# Processor_Board.net
KiCad netlist of a schematic drawn in EAGLE
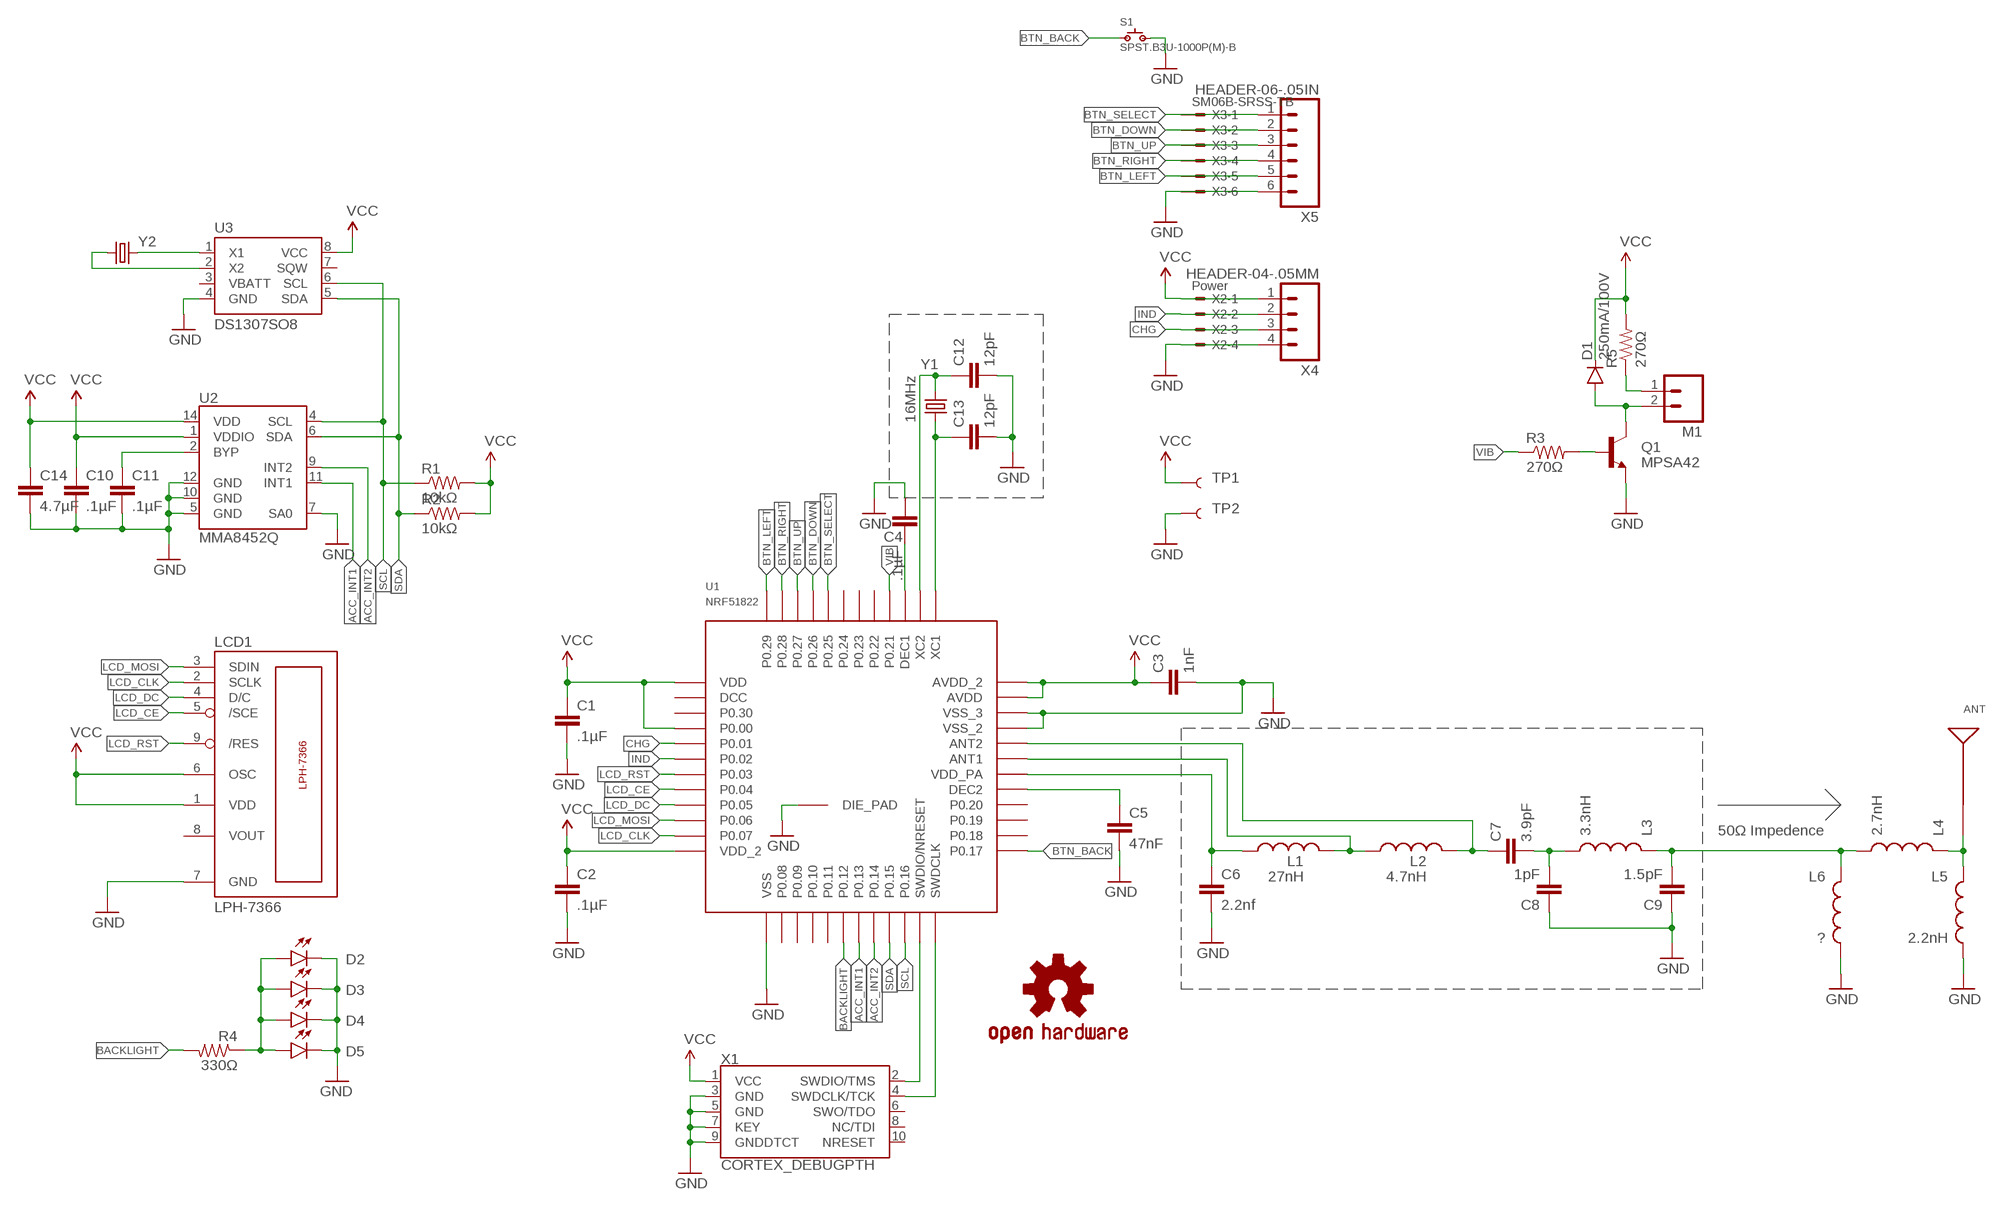
[diagram p0: schematic, sheet 1]

(export (version "E")
  (design (tool "Eeschema 10.0.6"))
  (components
    (comp (ref "ANT")
      (value "ANTENNA_CHIP2450AT43B100")
      (footprint "eagle-import:AT43B")
      (fields (field (name "MANUFACTURER") "Johanson Technology"))
      (libsource (lib "eagle-import") (part "ANTENNA_CHIP2450AT43B100"))
    )
    (comp (ref "C1")
      (value ".1µF")
      (footprint "eagle-import:0805")
      (libsource (lib "eagle-import") (part "CAP0805"))
    )
    (comp (ref "C2")
      (value ".1µF")
      (footprint "eagle-import:0805")
      (libsource (lib "eagle-import") (part "CAP0805"))
    )
    (comp (ref "C3")
      (value "1nF")
      (footprint "eagle-import:0805")
      (libsource (lib "eagle-import") (part "CAP0805"))
    )
    (comp (ref "C4")
      (value ".1µF")
      (footprint "eagle-import:0805")
      (libsource (lib "eagle-import") (part "CAP0805"))
    )
    (comp (ref "C5")
      (value "47nF")
      (footprint "eagle-import:0805")
      (libsource (lib "eagle-import") (part "CAP0805"))
    )
    (comp (ref "C6")
      (value "2.2nf")
      (footprint "eagle-import:0805")
      (libsource (lib "eagle-import") (part "CAP0805"))
    )
    (comp (ref "C7")
      (value "3.9pF")
      (footprint "eagle-import:0805")
      (libsource (lib "eagle-import") (part "CAP0805"))
    )
    (comp (ref "C8")
      (value "1pF")
      (footprint "eagle-import:0805")
      (libsource (lib "eagle-import") (part "CAP0805"))
    )
    (comp (ref "C9")
      (value "1.5pF")
      (footprint "eagle-import:0805")
      (libsource (lib "eagle-import") (part "CAP0805"))
    )
    (comp (ref "C10")
      (value ".1µF")
      (footprint "eagle-import:0805")
      (libsource (lib "eagle-import") (part "CAP0805"))
    )
    (comp (ref "C11")
      (value ".1µF")
      (footprint "eagle-import:0805")
      (libsource (lib "eagle-import") (part "CAP0805"))
    )
    (comp (ref "C12")
      (value "12pF")
      (footprint "eagle-import:0805")
      (libsource (lib "eagle-import") (part "CAP0805"))
    )
    (comp (ref "C13")
      (value "12pF")
      (footprint "eagle-import:0805")
      (libsource (lib "eagle-import") (part "CAP0805"))
    )
    (comp (ref "C14")
      (value "4.7µF")
      (footprint "eagle-import:0805")
      (libsource (lib "eagle-import") (part "CAP0805"))
    )
    (comp (ref "D1")
      (value "250mA/100V")
      (footprint "eagle-import:SOD-323")
      (libsource (lib "eagle-import") (part "DIODEBAS16"))
    )
    (comp (ref "D2")
      (value "LED1206")
      (footprint "eagle-import:LED-1206")
      (libsource (lib "eagle-import") (part "LED1206"))
    )
    (comp (ref "D3")
      (value "LED1206")
      (footprint "eagle-import:LED-1206")
      (libsource (lib "eagle-import") (part "LED1206"))
    )
    (comp (ref "D4")
      (value "LED1206")
      (footprint "eagle-import:LED-1206")
      (libsource (lib "eagle-import") (part "LED1206"))
    )
    (comp (ref "D5")
      (value "LED1206")
      (footprint "eagle-import:LED-1206")
      (libsource (lib "eagle-import") (part "LED1206"))
    )
    (comp (ref "L1")
      (value "27nH")
      (footprint "eagle-import:0805")
      (libsource (lib "eagle-import") (part "INDUCTOR0805"))
    )
    (comp (ref "L2")
      (value "4.7nH")
      (footprint "eagle-import:0805")
      (libsource (lib "eagle-import") (part "INDUCTOR0805"))
    )
    (comp (ref "L3")
      (value "3.3nH")
      (footprint "eagle-import:0805")
      (libsource (lib "eagle-import") (part "INDUCTOR0805"))
    )
    (comp (ref "L4")
      (value "2.7nH")
      (footprint "eagle-import:0805")
      (libsource (lib "eagle-import") (part "INDUCTOR0805"))
    )
    (comp (ref "L5")
      (value "2.2nH")
      (footprint "eagle-import:0805")
      (libsource (lib "eagle-import") (part "INDUCTOR0805"))
    )
    (comp (ref "L6")
      (value "?")
      (footprint "eagle-import:0805")
      (libsource (lib "eagle-import") (part "INDUCTOR0805"))
    )
    (comp (ref "LCD1")
      (value "LPH-7366")
      (footprint "eagle-import:LPH-7366")
      (libsource (lib "eagle-import") (part "LPH-7366"))
    )
    (comp (ref "LOGO1")
      (value "OSHW-LOGOL-COPPER")
      (footprint "eagle-import:OSHW-LOGO-L_COPPER")
      (libsource (lib "eagle-import") (part "OSHW-LOGOL-COPPER"))
    )
    (comp (ref "M1")
      (value "M021X02_NO_SILK")
      (footprint "eagle-import:1X02_NO_SILK")
      (libsource (lib "eagle-import") (part "M021X02_NO_SILK"))
    )
    (comp (ref "Q1")
      (value "MPSA42")
      (footprint "eagle-import:SOT23-3")
      (libsource (lib "eagle-import") (part "TRANSISTOR_NPNMPSA42"))
    )
    (comp (ref "R1")
      (value "10kΩ")
      (footprint "eagle-import:0805")
      (libsource (lib "eagle-import") (part "RESISTOR0805-RES"))
    )
    (comp (ref "R2")
      (value "10kΩ")
      (footprint "eagle-import:0805")
      (libsource (lib "eagle-import") (part "RESISTOR0805-RES"))
    )
    (comp (ref "R3")
      (value "270Ω")
      (footprint "eagle-import:0805")
      (libsource (lib "eagle-import") (part "RESISTOR0805-RES"))
    )
    (comp (ref "R4")
      (value "330Ω")
      (footprint "eagle-import:0805")
      (libsource (lib "eagle-import") (part "RESISTOR0805-RES"))
    )
    (comp (ref "R5")
      (value "270Ω")
      (footprint "eagle-import:0805")
      (libsource (lib "eagle-import") (part "RESISTOR0805-RES"))
    )
    (comp (ref "S1")
      (value "SPST.B3U-1000P(M)-B")
      (footprint "eagle-import:B3U-1000P(M)-B")
      (libsource (lib "eagle-import") (part "SPST.B3U-1000P(M)-B"))
    )
    (comp (ref "TP1")
      (value "TEST-POINT3")
      (footprint "eagle-import:PAD.03X.03")
      (libsource (lib "eagle-import") (part "TEST-POINT3"))
    )
    (comp (ref "TP2")
      (value "TEST-POINT3")
      (footprint "eagle-import:PAD.03X.03")
      (libsource (lib "eagle-import") (part "TEST-POINT3"))
    )
    (comp (ref "U1")
      (value "NRF51822")
      (footprint "eagle-import:QFN48")
      (libsource (lib "eagle-import") (part "NRF51822"))
    )
    (comp (ref "U2")
      (value "MMA8452Q")
      (footprint "eagle-import:QFN-16_0.5MM")
      (libsource (lib "eagle-import") (part "MMA8452Q"))
    )
    (comp (ref "U3")
      (value "DS1307SO8")
      (footprint "eagle-import:SO08")
      (libsource (lib "eagle-import") (part "DS1307SO8"))
    )
    (comp (ref "X1")
      (value "CORTEX_DEBUGPTH")
      (footprint "eagle-import:2X5-PTH-1.27MM")
      (libsource (lib "eagle-import") (part "CORTEX_DEBUGPTH"))
    )
    (comp (ref "X2")
      (value "Power")
      (footprint "eagle-import:SM04B-SRSS-TB")
      (libsource (lib "eagle-import") (part "?M04B-SRSS-TBS"))
    )
    (comp (ref "X3")
      (value "SM06B-SRSS-TB")
      (footprint "eagle-import:SM06B-SRSS-TB")
      (libsource (lib "eagle-import") (part "?M06B-SRSS-TBS"))
    )
    (comp (ref "X4")
      (value "HEADER-04-.05MM")
      (footprint "eagle-import:HEADER-04-.05IN")
      (libsource (lib "eagle-import") (part "HEADER-04-.05MM"))
    )
    (comp (ref "X5")
      (value "HEADER-06-.05IN")
      (footprint "eagle-import:HEADER-06-.05IN")
      (libsource (lib "eagle-import") (part "HEADER-06-.05IN"))
    )
    (comp (ref "Y1")
      (value "16MHz")
      (footprint "eagle-import:CRYSTAL-SMD-5X3")
      (libsource (lib "eagle-import") (part "CRYSTALCRYSTAL-SMD-5X3-16MHZ"))
    )
    (comp (ref "Y2")
      (value "CRYSTAL32-SMD-MELF")
      (footprint "eagle-import:CRYSTAL-32KHZ-SMD-MELF")
      (libsource (lib "eagle-import") (part "CRYSTAL32-SMD-MELF"))
    )
  )
  (nets
    (net (code "1") (name "ACC_INT1") (class "Default")
      (node (ref "U1") (pin "19") (pinfunction "P0.13_19") (pintype "bidirectional"))
      (node (ref "U2") (pin "11") (pinfunction "INT1_11") (pintype "bidirectional"))
    )
    (net (code "2") (name "ACC_INT2") (class "Default")
      (node (ref "U1") (pin "20") (pinfunction "P0.14_20") (pintype "bidirectional"))
      (node (ref "U2") (pin "9") (pinfunction "INT2_9") (pintype "bidirectional"))
    )
    (net (code "3") (name "BACKLIGHT") (class "Default")
      (node (ref "R4") (pin "2") (pinfunction "2_2") (pintype "passive"))
      (node (ref "U1") (pin "18") (pinfunction "P0.12_18") (pintype "bidirectional"))
    )
    (net (code "4") (name "BTN_BACK") (class "Default")
      (node (ref "S1") (pin "1") (pinfunction "1_1") (pintype "bidirectional"))
      (node (ref "U1") (pin "25") (pinfunction "P0.17_25") (pintype "bidirectional"))
    )
    (net (code "5") (name "BTN_DOWN") (class "Default")
      (node (ref "U1") (pin "45") (pinfunction "P0.26_45") (pintype "bidirectional"))
      (node (ref "X3") (pin "2") (pinfunction "S_2") (pintype "passive"))
      (node (ref "X5") (pin "2") (pinfunction "2_2") (pintype "passive"))
    )
    (net (code "6") (name "BTN_LEFT") (class "Default")
      (node (ref "U1") (pin "48") (pinfunction "P0.29_48") (pintype "bidirectional"))
      (node (ref "X3") (pin "5") (pinfunction "S_5") (pintype "passive"))
      (node (ref "X5") (pin "5") (pinfunction "5_5") (pintype "passive"))
    )
    (net (code "7") (name "BTN_RIGHT") (class "Default")
      (node (ref "U1") (pin "47") (pinfunction "P0.28_47") (pintype "bidirectional"))
      (node (ref "X3") (pin "4") (pinfunction "S_4") (pintype "passive"))
      (node (ref "X5") (pin "4") (pinfunction "4_4") (pintype "passive"))
    )
    (net (code "8") (name "BTN_SELECT") (class "Default")
      (node (ref "U1") (pin "44") (pinfunction "P0.25_44") (pintype "bidirectional"))
      (node (ref "X3") (pin "1") (pinfunction "S_1") (pintype "passive"))
      (node (ref "X5") (pin "1") (pinfunction "1_1") (pintype "passive"))
    )
    (net (code "9") (name "BTN_UP") (class "Default")
      (node (ref "U1") (pin "46") (pinfunction "P0.27_46") (pintype "bidirectional"))
      (node (ref "X3") (pin "3") (pinfunction "S_3") (pintype "passive"))
      (node (ref "X5") (pin "3") (pinfunction "3_3") (pintype "passive"))
    )
    (net (code "10") (name "CHG") (class "Default")
      (node (ref "U1") (pin "5") (pinfunction "P0.01_5") (pintype "bidirectional"))
      (node (ref "X2") (pin "3") (pinfunction "S_3") (pintype "passive"))
      (node (ref "X4") (pin "3") (pinfunction "3_3") (pintype "passive"))
    )
    (net (code "11") (name "GND") (class "Default")
      (node (ref "C1") (pin "2") (pinfunction "2_2") (pintype "passive"))
      (node (ref "C10") (pin "2") (pinfunction "2_2") (pintype "passive"))
      (node (ref "C11") (pin "2") (pinfunction "2_2") (pintype "passive"))
      (node (ref "C12") (pin "1") (pinfunction "1_1") (pintype "passive"))
      (node (ref "C13") (pin "1") (pinfunction "1_1") (pintype "passive"))
      (node (ref "C14") (pin "2") (pinfunction "2_2") (pintype "passive"))
      (node (ref "C2") (pin "2") (pinfunction "2_2") (pintype "passive"))
      (node (ref "C3") (pin "2") (pinfunction "2_2") (pintype "passive"))
      (node (ref "C4") (pin "1") (pinfunction "1_1") (pintype "passive"))
      (node (ref "C5") (pin "2") (pinfunction "2_2") (pintype "passive"))
      (node (ref "C6") (pin "2") (pinfunction "2_2") (pintype "passive"))
      (node (ref "C8") (pin "1") (pinfunction "1_1") (pintype "passive"))
      (node (ref "C9") (pin "1") (pinfunction "1_1") (pintype "passive"))
      (node (ref "D2") (pin "C") (pinfunction "C_C") (pintype "passive"))
      (node (ref "D3") (pin "C") (pinfunction "C_C") (pintype "passive"))
      (node (ref "D4") (pin "C") (pinfunction "C_C") (pintype "passive"))
      (node (ref "D5") (pin "C") (pinfunction "C_C") (pintype "passive"))
      (node (ref "L5") (pin "2") (pinfunction "2_2") (pintype "passive"))
      (node (ref "L6") (pin "2") (pinfunction "2_2") (pintype "passive"))
      (node (ref "LCD1") (pin "7") (pinfunction "GND_7") (pintype "power_in"))
      (node (ref "Q1") (pin "2") (pinfunction "E_2") (pintype "passive"))
      (node (ref "S1") (pin "2") (pinfunction "2_2") (pintype "bidirectional"))
      (node (ref "TP2") (pin "P$1") (pinfunction "1_P$1") (pintype "bidirectional"))
      (node (ref "U1") (pin "13") (pinfunction "VSS_13") (pintype "bidirectional"))
      (node (ref "U1") (pin "33") (pinfunction "VSS_2_33") (pintype "bidirectional"))
      (node (ref "U1") (pin "34") (pinfunction "VSS_3_34") (pintype "bidirectional"))
      (node (ref "U1") (pin "GND") (pinfunction "DIE_PAD_GND") (pintype "bidirectional"))
      (node (ref "U2") (pin "10") (pinfunction "GND_10") (pintype "bidirectional"))
      (node (ref "U2") (pin "12") (pinfunction "GND_12") (pintype "bidirectional"))
      (node (ref "U2") (pin "5") (pinfunction "GND_5") (pintype "bidirectional"))
      (node (ref "U2") (pin "7") (pinfunction "SA0_7") (pintype "bidirectional"))
      (node (ref "U3") (pin "4") (pinfunction "GND_4") (pintype "bidirectional"))
      (node (ref "X1") (pin "3") (pinfunction "GND_3") (pintype "bidirectional"))
      (node (ref "X1") (pin "5") (pinfunction "GND_5") (pintype "bidirectional"))
      (node (ref "X1") (pin "7") (pinfunction "KEY_7") (pintype "bidirectional"))
      (node (ref "X1") (pin "9") (pinfunction "GNDDTCT_9") (pintype "bidirectional"))
      (node (ref "X2") (pin "4") (pinfunction "S_4") (pintype "passive"))
      (node (ref "X3") (pin "6") (pinfunction "S_6") (pintype "passive"))
      (node (ref "X4") (pin "4") (pinfunction "4_4") (pintype "passive"))
      (node (ref "X5") (pin "6") (pinfunction "6_6") (pintype "passive"))
    )
    (net (code "12") (name "IND") (class "Default")
      (node (ref "U1") (pin "6") (pinfunction "P0.02_6") (pintype "bidirectional"))
      (node (ref "X2") (pin "2") (pinfunction "S_2") (pintype "passive"))
      (node (ref "X4") (pin "2") (pinfunction "2_2") (pintype "passive"))
    )
    (net (code "13") (name "LCD_CE") (class "Default")
      (node (ref "LCD1") (pin "5") (pinfunction "/SCE_5") (pintype "input"))
      (node (ref "U1") (pin "8") (pinfunction "P0.04_8") (pintype "bidirectional"))
    )
    (net (code "14") (name "LCD_CLK") (class "Default")
      (node (ref "LCD1") (pin "2") (pinfunction "SCLK_2") (pintype "input"))
      (node (ref "U1") (pin "11") (pinfunction "P0.07_11") (pintype "bidirectional"))
    )
    (net (code "15") (name "LCD_DC") (class "Default")
      (node (ref "LCD1") (pin "4") (pinfunction "D/C_4") (pintype "input"))
      (node (ref "U1") (pin "9") (pinfunction "P0.05_9") (pintype "bidirectional"))
    )
    (net (code "16") (name "LCD_MOSI") (class "Default")
      (node (ref "LCD1") (pin "3") (pinfunction "SDIN_3") (pintype "input"))
      (node (ref "U1") (pin "10") (pinfunction "P0.06_10") (pintype "bidirectional"))
    )
    (net (code "17") (name "LCD_RST") (class "Default")
      (node (ref "LCD1") (pin "9") (pinfunction "/RES_9") (pintype "input"))
      (node (ref "U1") (pin "7") (pinfunction "P0.03_7") (pintype "bidirectional"))
    )
    (net (code "18") (name "Net-(ANT-PadANT)") (class "Default")
      (node (ref "ANT") (pin "ANT") (pinfunction "ANT_ANT") (pintype "bidirectional"))
      (node (ref "L4") (pin "1") (pinfunction "1_1") (pintype "passive"))
      (node (ref "L5") (pin "1") (pinfunction "1_1") (pintype "passive"))
    )
    (net (code "19") (name "Net-(C7-Pad2)") (class "Default")
      (node (ref "C7") (pin "2") (pinfunction "2_2") (pintype "passive"))
      (node (ref "C8") (pin "2") (pinfunction "2_2") (pintype "passive"))
      (node (ref "L3") (pin "2") (pinfunction "2_2") (pintype "passive"))
    )
    (net (code "20") (name "Net-(C9-Pad2)") (class "Default")
      (node (ref "C9") (pin "2") (pinfunction "2_2") (pintype "passive"))
      (node (ref "L3") (pin "1") (pinfunction "1_1") (pintype "passive"))
      (node (ref "L4") (pin "2") (pinfunction "2_2") (pintype "passive"))
      (node (ref "L6") (pin "1") (pinfunction "1_1") (pintype "passive"))
    )
    (net (code "21") (name "Net-(D2-PadA)") (class "Default")
      (node (ref "D2") (pin "A") (pinfunction "A_A") (pintype "passive"))
      (node (ref "D3") (pin "A") (pinfunction "A_A") (pintype "passive"))
      (node (ref "D4") (pin "A") (pinfunction "A_A") (pintype "passive"))
      (node (ref "D5") (pin "A") (pinfunction "A_A") (pintype "passive"))
      (node (ref "R4") (pin "1") (pinfunction "1_1") (pintype "passive"))
    )
    (net (code "22") (name "Net-(M1-Pad1)") (class "Default")
      (node (ref "M1") (pin "1") (pinfunction "1_1") (pintype "passive"))
      (node (ref "R5") (pin "1") (pinfunction "1_1") (pintype "passive"))
    )
    (net (code "23") (name "Net-(Q1-B)") (class "Default")
      (node (ref "Q1") (pin "1") (pinfunction "B_1") (pintype "passive"))
      (node (ref "R3") (pin "2") (pinfunction "2_2") (pintype "passive"))
    )
    (net (code "24") (name "Net-(Q1-C)") (class "Default")
      (node (ref "D1") (pin "A") (pinfunction "A_A") (pintype "passive"))
      (node (ref "M1") (pin "2") (pinfunction "2_2") (pintype "passive"))
      (node (ref "Q1") (pin "3") (pinfunction "C_3") (pintype "passive"))
    )
    (net (code "25") (name "Net-(U1-ANT1)") (class "Default")
      (node (ref "L1") (pin "1") (pinfunction "1_1") (pintype "passive"))
      (node (ref "L2") (pin "2") (pinfunction "2_2") (pintype "passive"))
      (node (ref "U1") (pin "31") (pinfunction "ANT1_31") (pintype "bidirectional"))
    )
    (net (code "26") (name "Net-(U1-ANT2)") (class "Default")
      (node (ref "C7") (pin "1") (pinfunction "1_1") (pintype "passive"))
      (node (ref "L2") (pin "1") (pinfunction "1_1") (pintype "passive"))
      (node (ref "U1") (pin "32") (pinfunction "ANT2_32") (pintype "bidirectional"))
    )
    (net (code "27") (name "Net-(U1-DEC1)") (class "Default")
      (node (ref "C4") (pin "2") (pinfunction "2_2") (pintype "passive"))
      (node (ref "U1") (pin "39") (pinfunction "DEC1_39") (pintype "bidirectional"))
    )
    (net (code "28") (name "Net-(U1-DEC2)") (class "Default")
      (node (ref "C5") (pin "1") (pinfunction "1_1") (pintype "passive"))
      (node (ref "U1") (pin "29") (pinfunction "DEC2_29") (pintype "bidirectional"))
    )
    (net (code "29") (name "Net-(U1-SWDCLK)") (class "Default")
      (node (ref "U1") (pin "24") (pinfunction "SWDCLK_24") (pintype "bidirectional"))
      (node (ref "X1") (pin "4") (pinfunction "SWDCLK/TCK_4") (pintype "bidirectional"))
    )
    (net (code "30") (name "Net-(U1-SWDIO{slash}NRESET)") (class "Default")
      (node (ref "U1") (pin "23") (pinfunction "SWDIO/NRESET_23") (pintype "bidirectional"))
      (node (ref "X1") (pin "2") (pinfunction "SWDIO/TMS_2") (pintype "bidirectional"))
    )
    (net (code "31") (name "Net-(U1-VDD_PA)") (class "Default")
      (node (ref "C6") (pin "1") (pinfunction "1_1") (pintype "passive"))
      (node (ref "L1") (pin "2") (pinfunction "2_2") (pintype "passive"))
      (node (ref "U1") (pin "30") (pinfunction "VDD_PA_30") (pintype "bidirectional"))
    )
    (net (code "32") (name "Net-(U1-XC1)") (class "Default")
      (node (ref "C13") (pin "2") (pinfunction "2_2") (pintype "passive"))
      (node (ref "U1") (pin "37") (pinfunction "XC1_37") (pintype "bidirectional"))
      (node (ref "Y1") (pin "1") (pinfunction "1_1") (pintype "passive"))
    )
    (net (code "33") (name "Net-(U1-XC2)") (class "Default")
      (node (ref "C12") (pin "2") (pinfunction "2_2") (pintype "passive"))
      (node (ref "U1") (pin "38") (pinfunction "XC2_38") (pintype "bidirectional"))
      (node (ref "Y1") (pin "3") (pinfunction "2_3") (pintype "passive"))
    )
    (net (code "34") (name "Net-(U2-BYP)") (class "Default")
      (node (ref "C11") (pin "1") (pinfunction "1_1") (pintype "passive"))
      (node (ref "U2") (pin "2") (pinfunction "BYP_2") (pintype "bidirectional"))
    )
    (net (code "35") (name "Net-(U3-X1)") (class "Default")
      (node (ref "U3") (pin "1") (pinfunction "X1_1") (pintype "bidirectional"))
      (node (ref "Y2") (pin "X2") (pinfunction "2_X2") (pintype "passive"))
    )
    (net (code "36") (name "Net-(U3-X2)") (class "Default")
      (node (ref "U3") (pin "2") (pinfunction "X2_2") (pintype "bidirectional"))
      (node (ref "Y2") (pin "X1") (pinfunction "1_X1") (pintype "passive"))
    )
    (net (code "37") (name "SCL") (class "Default")
      (node (ref "R1") (pin "1") (pinfunction "1_1") (pintype "passive"))
      (node (ref "U1") (pin "22") (pinfunction "P0.16_22") (pintype "bidirectional"))
      (node (ref "U2") (pin "4") (pinfunction "SCL_4") (pintype "bidirectional"))
      (node (ref "U3") (pin "6") (pinfunction "SCL_6") (pintype "bidirectional"))
    )
    (net (code "38") (name "SDA") (class "Default")
      (node (ref "R2") (pin "1") (pinfunction "1_1") (pintype "passive"))
      (node (ref "U1") (pin "21") (pinfunction "P0.15_21") (pintype "bidirectional"))
      (node (ref "U2") (pin "6") (pinfunction "SDA_6") (pintype "bidirectional"))
      (node (ref "U3") (pin "5") (pinfunction "SDA_5") (pintype "bidirectional"))
    )
    (net (code "39") (name "VCC") (class "Default")
      (node (ref "C1") (pin "1") (pinfunction "1_1") (pintype "passive"))
      (node (ref "C10") (pin "1") (pinfunction "1_1") (pintype "passive"))
      (node (ref "C14") (pin "1") (pinfunction "1_1") (pintype "passive"))
      (node (ref "C2") (pin "1") (pinfunction "1_1") (pintype "passive"))
      (node (ref "C3") (pin "1") (pinfunction "1_1") (pintype "passive"))
      (node (ref "D1") (pin "C") (pinfunction "C_C") (pintype "passive"))
      (node (ref "LCD1") (pin "1") (pinfunction "VDD_1") (pintype "power_in"))
      (node (ref "LCD1") (pin "6") (pinfunction "OSC_6") (pintype "passive"))
      (node (ref "R1") (pin "2") (pinfunction "2_2") (pintype "passive"))
      (node (ref "R2") (pin "2") (pinfunction "2_2") (pintype "passive"))
      (node (ref "R5") (pin "2") (pinfunction "2_2") (pintype "passive"))
      (node (ref "TP1") (pin "P$1") (pinfunction "1_P$1") (pintype "bidirectional"))
      (node (ref "U1") (pin "1") (pinfunction "VDD_1") (pintype "bidirectional"))
      (node (ref "U1") (pin "12") (pinfunction "VDD_2_12") (pintype "bidirectional"))
      (node (ref "U1") (pin "35") (pinfunction "AVDD_35") (pintype "bidirectional"))
      (node (ref "U1") (pin "36") (pinfunction "AVDD_2_36") (pintype "bidirectional"))
      (node (ref "U1") (pin "4") (pinfunction "P0.00_4") (pintype "bidirectional"))
      (node (ref "U2") (pin "1") (pinfunction "VDDIO_1") (pintype "bidirectional"))
      (node (ref "U2") (pin "14") (pinfunction "VDD_14") (pintype "bidirectional"))
      (node (ref "U3") (pin "8") (pinfunction "VCC_8") (pintype "bidirectional"))
      (node (ref "X1") (pin "1") (pinfunction "VCC_1") (pintype "bidirectional"))
      (node (ref "X2") (pin "1") (pinfunction "S_1") (pintype "passive"))
      (node (ref "X4") (pin "1") (pinfunction "1_1") (pintype "passive"))
    )
    (net (code "40") (name "VIB") (class "Default")
      (node (ref "R3") (pin "1") (pinfunction "1_1") (pintype "passive"))
      (node (ref "U1") (pin "40") (pinfunction "P0.21_40") (pintype "bidirectional"))
    )
    (net (code "41") (name "unconnected-(LCD1-VOUT-Pad8)") (class "Default")
      (node (ref "LCD1") (pin "8") (pinfunction "VOUT_8") (pintype "passive"))
    )
    (net (code "42") (name "unconnected-(U1-DCC-Pad2)") (class "Default")
      (node (ref "U1") (pin "2") (pinfunction "DCC_2") (pintype "bidirectional"))
    )
    (net (code "43") (name "unconnected-(U1-P0.08-Pad14)") (class "Default")
      (node (ref "U1") (pin "14") (pinfunction "P0.08_14") (pintype "bidirectional"))
    )
    (net (code "44") (name "unconnected-(U1-P0.09-Pad15)") (class "Default")
      (node (ref "U1") (pin "15") (pinfunction "P0.09_15") (pintype "bidirectional"))
    )
    (net (code "45") (name "unconnected-(U1-P0.10-Pad16)") (class "Default")
      (node (ref "U1") (pin "16") (pinfunction "P0.10_16") (pintype "bidirectional"))
    )
    (net (code "46") (name "unconnected-(U1-P0.11-Pad17)") (class "Default")
      (node (ref "U1") (pin "17") (pinfunction "P0.11_17") (pintype "bidirectional"))
    )
    (net (code "47") (name "unconnected-(U1-P0.18-Pad26)") (class "Default")
      (node (ref "U1") (pin "26") (pinfunction "P0.18_26") (pintype "bidirectional"))
    )
    (net (code "48") (name "unconnected-(U1-P0.19-Pad27)") (class "Default")
      (node (ref "U1") (pin "27") (pinfunction "P0.19_27") (pintype "bidirectional"))
    )
    (net (code "49") (name "unconnected-(U1-P0.20-Pad28)") (class "Default")
      (node (ref "U1") (pin "28") (pinfunction "P0.20_28") (pintype "bidirectional"))
    )
    (net (code "50") (name "unconnected-(U1-P0.22-Pad41)") (class "Default")
      (node (ref "U1") (pin "41") (pinfunction "P0.22_41") (pintype "bidirectional"))
    )
    (net (code "51") (name "unconnected-(U1-P0.23-Pad42)") (class "Default")
      (node (ref "U1") (pin "42") (pinfunction "P0.23_42") (pintype "bidirectional"))
    )
    (net (code "52") (name "unconnected-(U1-P0.24-Pad43)") (class "Default")
      (node (ref "U1") (pin "43") (pinfunction "P0.24_43") (pintype "bidirectional"))
    )
    (net (code "53") (name "unconnected-(U1-P0.30-Pad3)") (class "Default")
      (node (ref "U1") (pin "3") (pinfunction "P0.30_3") (pintype "bidirectional"))
    )
    (net (code "54") (name "unconnected-(U3-SQW-Pad7)") (class "Default")
      (node (ref "U3") (pin "7") (pinfunction "SQW_7") (pintype "bidirectional"))
    )
    (net (code "55") (name "unconnected-(U3-VBATT-Pad3)") (class "Default")
      (node (ref "U3") (pin "3") (pinfunction "VBATT_3") (pintype "bidirectional"))
    )
    (net (code "56") (name "unconnected-(X1-NC{slash}TDI-Pad8)") (class "Default")
      (node (ref "X1") (pin "8") (pinfunction "NC/TDI_8") (pintype "bidirectional"))
    )
    (net (code "57") (name "unconnected-(X1-NRESET-Pad10)") (class "Default")
      (node (ref "X1") (pin "10") (pinfunction "NRESET_10") (pintype "bidirectional"))
    )
    (net (code "58") (name "unconnected-(X1-SWO{slash}TDO-Pad6)") (class "Default")
      (node (ref "X1") (pin "6") (pinfunction "SWO/TDO_6") (pintype "bidirectional"))
    )
  )
)
